# externalConnections.net
KiCad netlist of a schematic drawn in Altium Designer
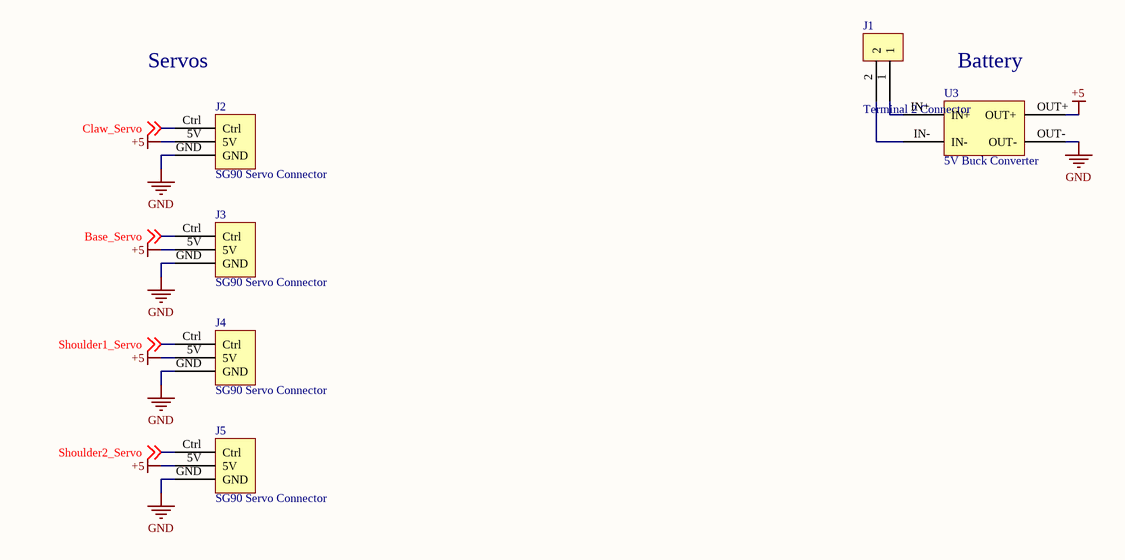
[diagram p0: externalConnections.SchDoc]

(export (version "E")
  (design (tool "Eeschema 10.0.6"))
  (components
    (comp (ref "J1")
      (value "Terminal 2 Connector")
      (footprint "Terminal 2 Connector")
      (description "https://jlcpcb.com/partdetail/Ningbo_KangnexElec-WJ500V_5_082P/C8465")
      (libsource (lib "MindControlledCarPCB") (part "Terminal 2 Connector"))
    )
    (comp (ref "J2")
      (value "SG90 Servo Connector")
      (footprint "SG90 Servo Connector")
      (libsource (lib "MindControlledCarPCB") (part "SG90 Servo Connector"))
    )
    (comp (ref "J3")
      (value "SG90 Servo Connector")
      (footprint "SG90 Servo Connector")
      (libsource (lib "MindControlledCarPCB") (part "SG90 Servo Connector"))
    )
    (comp (ref "J4")
      (value "SG90 Servo Connector")
      (footprint "SG90 Servo Connector")
      (libsource (lib "MindControlledCarPCB") (part "SG90 Servo Connector"))
    )
    (comp (ref "J5")
      (value "SG90 Servo Connector")
      (footprint "SG90 Servo Connector")
      (libsource (lib "MindControlledCarPCB") (part "SG90 Servo Connector"))
    )
    (comp (ref "U3")
      (value "5V Buck Converter")
      (footprint "5V Buck Converter")
      (libsource (lib "MindControlledCarPCB") (part "5V Buck Converter"))
    )
  )
  (nets
    (net (code "1") (name "+5") (class "Default")
      (node (ref "J2") (pin "5V") (pinfunction "5V_5V") (pintype "passive"))
      (node (ref "J3") (pin "5V") (pinfunction "5V_5V") (pintype "passive"))
      (node (ref "J4") (pin "5V") (pinfunction "5V_5V") (pintype "passive"))
      (node (ref "J5") (pin "5V") (pinfunction "5V_5V") (pintype "passive"))
      (node (ref "U3") (pin "OUT+") (pinfunction "OUT+_OUT+") (pintype "passive"))
    )
    (net (code "2") (name "Base_Servo") (class "Default")
      (node (ref "J3") (pin "Ctrl") (pinfunction "Ctrl_Ctrl") (pintype "passive"))
    )
    (net (code "3") (name "Claw_Servo") (class "Default")
      (node (ref "J2") (pin "Ctrl") (pinfunction "Ctrl_Ctrl") (pintype "passive"))
    )
    (net (code "4") (name "GND") (class "Default")
      (node (ref "J2") (pin "GND") (pinfunction "GND_GND") (pintype "passive"))
      (node (ref "J3") (pin "GND") (pinfunction "GND_GND") (pintype "passive"))
      (node (ref "J4") (pin "GND") (pinfunction "GND_GND") (pintype "passive"))
      (node (ref "J5") (pin "GND") (pinfunction "GND_GND") (pintype "passive"))
      (node (ref "U3") (pin "OUT-") (pinfunction "OUT-_OUT-") (pintype "passive"))
    )
    (net (code "5") (name "Net-(J1-Pad1)") (class "Default")
      (node (ref "J1") (pin "1") (pinfunction "1_1") (pintype "passive"))
      (node (ref "U3") (pin "IN+") (pinfunction "IN+_IN+") (pintype "passive"))
    )
    (net (code "6") (name "Net-(J1-Pad2)") (class "Default")
      (node (ref "J1") (pin "2") (pinfunction "2_2") (pintype "passive"))
      (node (ref "U3") (pin "IN-") (pinfunction "IN-_IN-") (pintype "passive"))
    )
    (net (code "7") (name "Shoulder1_Servo") (class "Default")
      (node (ref "J4") (pin "Ctrl") (pinfunction "Ctrl_Ctrl") (pintype "passive"))
    )
    (net (code "8") (name "Shoulder2_Servo") (class "Default")
      (node (ref "J5") (pin "Ctrl") (pinfunction "Ctrl_Ctrl") (pintype "passive"))
    )
  )
)
